# BV100011_ControlAO.net
KiCad netlist of a schematic drawn in Altium Designer
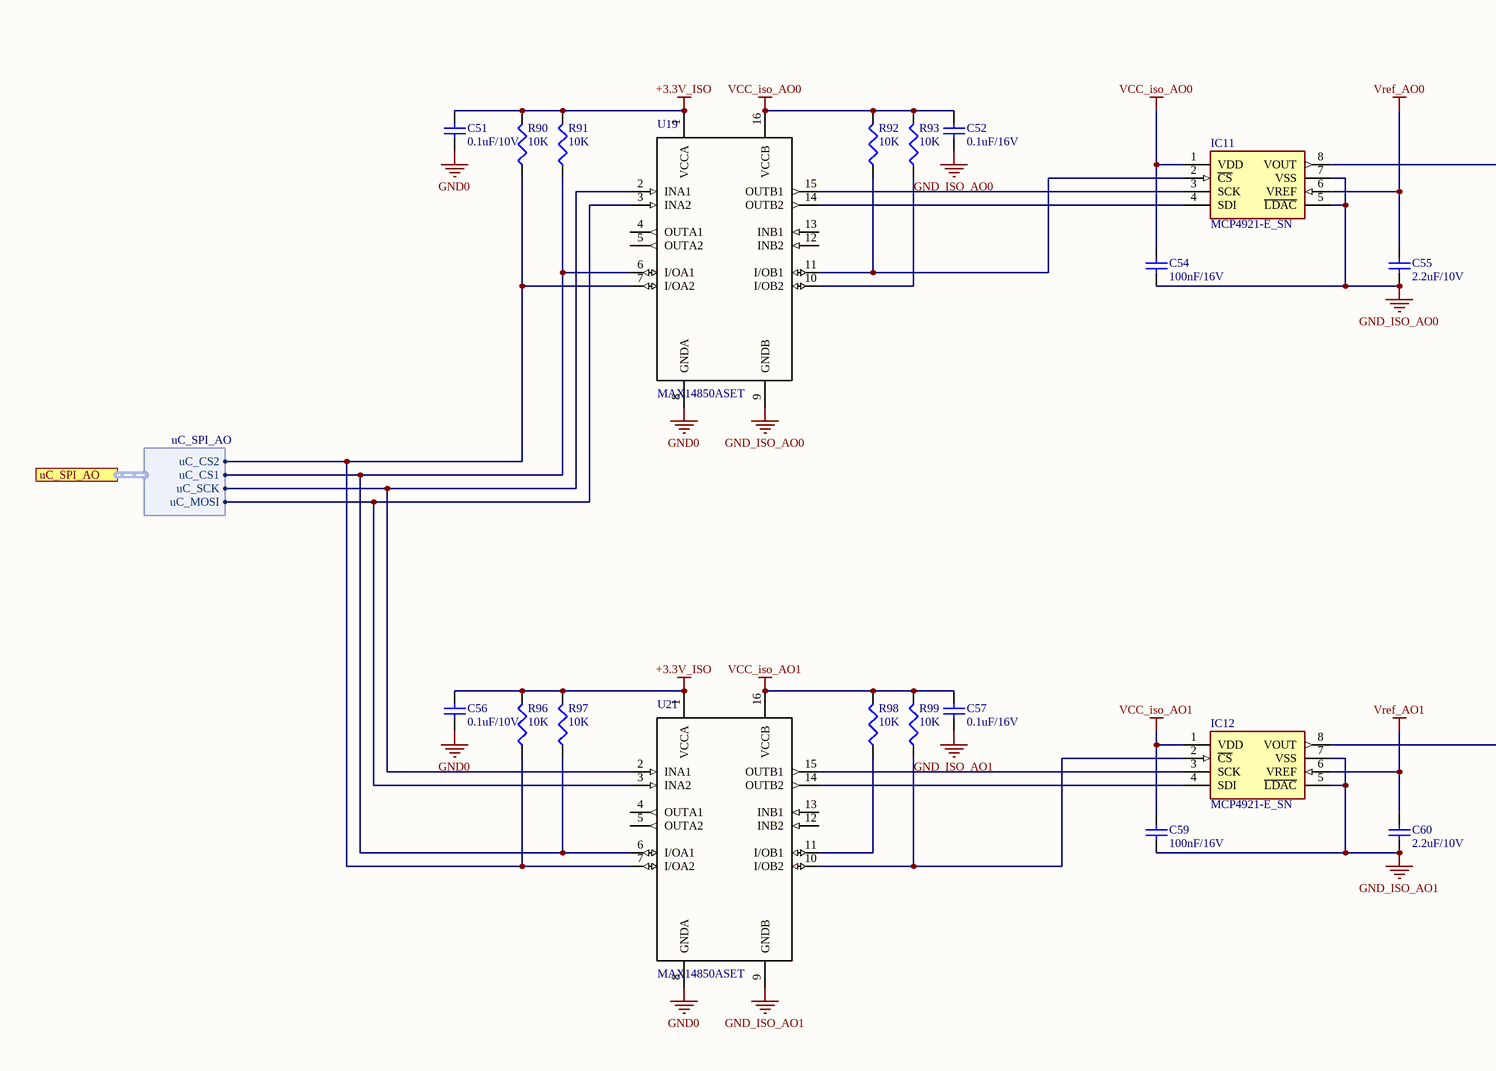
[diagram p0: BV100011_ControlAO.SchDoc, left]
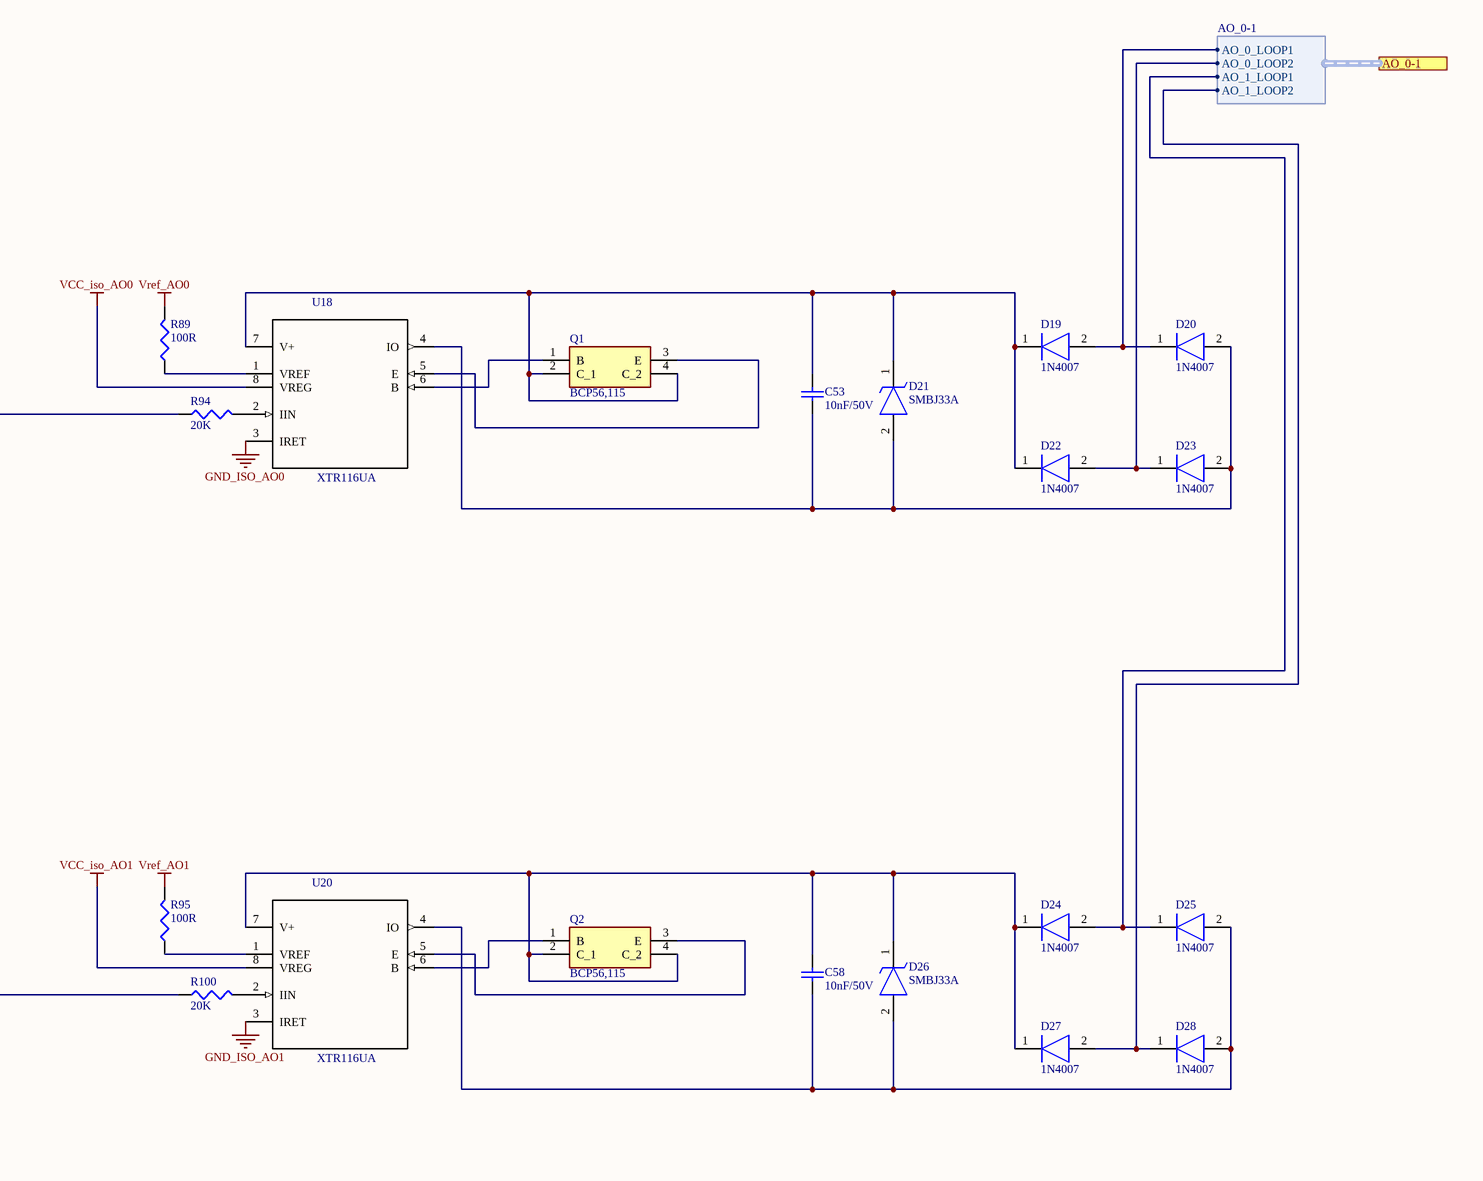
[diagram p1: BV100011_ControlAO.SchDoc, right]

(export (version "E")
  (design (tool "Eeschema 10.0.6"))
  (components
    (comp (ref "C51")
      (value "0.1uF/10V")
      (footprint "C1206")
      (description "Capacitor (Semiconductor SIM Model)")
      (fields (field (name "PUBLISHER") "Altium Limited"))
      (libsource (lib "Miscellaneous Devices") (part "Cap Semi"))
    )
    (comp (ref "C52")
      (value "0.1uF/16V")
      (footprint "C1206")
      (description "Capacitor (Semiconductor SIM Model)")
      (fields (field (name "PUBLISHER") "Altium Limited"))
      (libsource (lib "Miscellaneous Devices") (part "Cap Semi"))
    )
    (comp (ref "C53")
      (value "10nF/50V")
      (footprint "C1210")
      (description "Capacitor (Semiconductor SIM Model)")
      (fields (field (name "PUBLISHER") "Altium Limited"))
      (libsource (lib "Miscellaneous Devices") (part "Cap Semi"))
    )
    (comp (ref "C54")
      (value "100nF/16V")
      (footprint "C1206")
      (description "Capacitor (Semiconductor SIM Model)")
      (fields (field (name "PUBLISHER") "Altium Limited"))
      (libsource (lib "Miscellaneous Devices") (part "Cap Semi"))
    )
    (comp (ref "C55")
      (value "2.2uF/10V")
      (footprint "C1206")
      (description "Capacitor (Semiconductor SIM Model)")
      (fields (field (name "PUBLISHER") "Altium Limited"))
      (libsource (lib "Miscellaneous Devices") (part "Cap Semi"))
    )
    (comp (ref "C56")
      (value "0.1uF/10V")
      (footprint "C1206")
      (description "Capacitor (Semiconductor SIM Model)")
      (fields (field (name "PUBLISHER") "Altium Limited"))
      (libsource (lib "Miscellaneous Devices") (part "Cap Semi"))
    )
    (comp (ref "C57")
      (value "0.1uF/16V")
      (footprint "C1206")
      (description "Capacitor (Semiconductor SIM Model)")
      (fields (field (name "PUBLISHER") "Altium Limited"))
      (libsource (lib "Miscellaneous Devices") (part "Cap Semi"))
    )
    (comp (ref "C58")
      (value "10nF/50V")
      (footprint "C1210")
      (description "Capacitor (Semiconductor SIM Model)")
      (fields (field (name "PUBLISHER") "Altium Limited"))
      (libsource (lib "Miscellaneous Devices") (part "Cap Semi"))
    )
    (comp (ref "C59")
      (value "100nF/16V")
      (footprint "C1206")
      (description "Capacitor (Semiconductor SIM Model)")
      (fields (field (name "PUBLISHER") "Altium Limited"))
      (libsource (lib "Miscellaneous Devices") (part "Cap Semi"))
    )
    (comp (ref "C60")
      (value "2.2uF/10V")
      (footprint "C1206")
      (description "Capacitor (Semiconductor SIM Model)")
      (fields (field (name "PUBLISHER") "Altium Limited"))
      (libsource (lib "Miscellaneous Devices") (part "Cap Semi"))
    )
    (comp (ref "D19")
      (value "1N4007")
      (footprint "DIOM5327X242N")
      (description "Diode")
      (libsource (lib "1N4007") (part "1N4007"))
    )
    (comp (ref "D20")
      (value "1N4007")
      (footprint "DIOM5327X242N")
      (description "Diode")
      (libsource (lib "1N4007") (part "1N4007"))
    )
    (comp (ref "D21")
      (value "SMBJ33A")
      (footprint "DIOM5336X265N")
      (description "TVS Diode (Uni-directional)")
      (fields (field (name "MOUSER PART NUMBER") "512-SMBJ33A") (field (name "RS PART NUMBER") "8022320P"))
      (libsource (lib "SMBJ33A") (part "SMBJ33A"))
    )
    (comp (ref "D22")
      (value "1N4007")
      (footprint "DIOM5327X242N")
      (description "Diode")
      (libsource (lib "1N4007") (part "1N4007"))
    )
    (comp (ref "D23")
      (value "1N4007")
      (footprint "DIOM5327X242N")
      (description "Diode")
      (libsource (lib "1N4007") (part "1N4007"))
    )
    (comp (ref "D24")
      (value "1N4007")
      (footprint "DIOM5327X242N")
      (description "Diode")
      (libsource (lib "1N4007") (part "1N4007"))
    )
    (comp (ref "D25")
      (value "1N4007")
      (footprint "DIOM5327X242N")
      (description "Diode")
      (libsource (lib "1N4007") (part "1N4007"))
    )
    (comp (ref "D26")
      (value "SMBJ33A")
      (footprint "DIOM5336X265N")
      (description "TVS Diode (Uni-directional)")
      (fields (field (name "MOUSER PART NUMBER") "512-SMBJ33A") (field (name "RS PART NUMBER") "8022320P"))
      (libsource (lib "SMBJ33A") (part "SMBJ33A"))
    )
    (comp (ref "D27")
      (value "1N4007")
      (footprint "DIOM5327X242N")
      (description "Diode")
      (libsource (lib "1N4007") (part "1N4007"))
    )
    (comp (ref "D28")
      (value "1N4007")
      (footprint "DIOM5327X242N")
      (description "Diode")
      (libsource (lib "1N4007") (part "1N4007"))
    )
    (comp (ref "IC11")
      (value "MCP4921-E_SN")
      (footprint "SOIC127P600X175-8N")
      (description "Integrated Circuit")
      (fields
        (field (name "MANUFACTURER_PART_NUMBER") "MCP4921-E/SN")
        (field (name "MOUSER PART NUMBER") "579-MCP4921-E/SN")
      )
      (libsource (lib "MCP4921") (part "MCP4921-E_SN"))
    )
    (comp (ref "IC12")
      (value "MCP4921-E_SN")
      (footprint "SOIC127P600X175-8N")
      (description "Integrated Circuit")
      (fields
        (field (name "MANUFACTURER_PART_NUMBER") "MCP4921-E/SN")
        (field (name "MOUSER PART NUMBER") "579-MCP4921-E/SN")
      )
      (libsource (lib "MCP4921") (part "MCP4921-E_SN"))
    )
    (comp (ref "Q1")
      (value "BCP56,115")
      (footprint "SOT230P700X180-4N")
      (description "Transistor BJT NPN")
      (fields (field (name "MOUSER PART NUMBER") "771-BCP56-T/R") (field (name "RS PART NUMBER") "1125453P"))
      (libsource (lib "BCP56") (part "BCP56,115"))
    )
    (comp (ref "Q2")
      (value "BCP56,115")
      (footprint "SOT230P700X180-4N")
      (description "Transistor BJT NPN")
      (fields (field (name "MOUSER PART NUMBER") "771-BCP56-T/R") (field (name "RS PART NUMBER") "1125453P"))
      (libsource (lib "BCP56") (part "BCP56,115"))
    )
    (comp (ref "R89")
      (value "100R")
      (footprint "J1-0603")
      (description "Resistor")
      (fields (field (name "PUBLISHER") "Altium Limited"))
      (libsource (lib "Miscellaneous Devices") (part "Res3"))
    )
    (comp (ref "R90")
      (value "10K")
      (footprint "J1-0603")
      (description "Resistor")
      (fields (field (name "PUBLISHER") "Altium Limited"))
      (libsource (lib "Miscellaneous Devices") (part "Res3"))
    )
    (comp (ref "R91")
      (value "10K")
      (footprint "J1-0603")
      (description "Resistor")
      (fields (field (name "PUBLISHER") "Altium Limited"))
      (libsource (lib "Miscellaneous Devices") (part "Res3"))
    )
    (comp (ref "R92")
      (value "10K")
      (footprint "J1-0603")
      (description "Resistor")
      (fields (field (name "PUBLISHER") "Altium Limited"))
      (libsource (lib "Miscellaneous Devices") (part "Res3"))
    )
    (comp (ref "R93")
      (value "10K")
      (footprint "J1-0603")
      (description "Resistor")
      (fields (field (name "PUBLISHER") "Altium Limited"))
      (libsource (lib "Miscellaneous Devices") (part "Res3"))
    )
    (comp (ref "R94")
      (value "20K")
      (footprint "J1-0603")
      (description "Resistor")
      (fields (field (name "PUBLISHER") "Altium Limited"))
      (libsource (lib "Miscellaneous Devices") (part "Res3"))
    )
    (comp (ref "R95")
      (value "100R")
      (footprint "J1-0603")
      (description "Resistor")
      (fields (field (name "PUBLISHER") "Altium Limited"))
      (libsource (lib "Miscellaneous Devices") (part "Res3"))
    )
    (comp (ref "R96")
      (value "10K")
      (footprint "J1-0603")
      (description "Resistor")
      (fields (field (name "PUBLISHER") "Altium Limited"))
      (libsource (lib "Miscellaneous Devices") (part "Res3"))
    )
    (comp (ref "R97")
      (value "10K")
      (footprint "J1-0603")
      (description "Resistor")
      (fields (field (name "PUBLISHER") "Altium Limited"))
      (libsource (lib "Miscellaneous Devices") (part "Res3"))
    )
    (comp (ref "R98")
      (value "10K")
      (footprint "J1-0603")
      (description "Resistor")
      (fields (field (name "PUBLISHER") "Altium Limited"))
      (libsource (lib "Miscellaneous Devices") (part "Res3"))
    )
    (comp (ref "R99")
      (value "10K")
      (footprint "J1-0603")
      (description "Resistor")
      (fields (field (name "PUBLISHER") "Altium Limited"))
      (libsource (lib "Miscellaneous Devices") (part "Res3"))
    )
    (comp (ref "R100")
      (value "20K")
      (footprint "J1-0603")
      (description "Resistor")
      (fields (field (name "PUBLISHER") "Altium Limited"))
      (libsource (lib "Miscellaneous Devices") (part "Res3"))
    )
    (comp (ref "U18")
      (value "XTR116UA")
      (footprint "*SOIC127P600X175-8N")
      (description "Sensors, Sensor Conditioning, 4-20mA Transmitters 4-20mA Current Loop Transmitters")
      (fields (field (name "MF") "Texas Instruments"))
      (libsource (lib "XTR116UA") (part "XTR116UA"))
    )
    (comp (ref "U19")
      (value "MAX14850ASET")
      (footprint "*SOIC127P600X175-16N")
      (description "Digital Isolator, 6-Ch, 30ns, Nsoic-16")
      (fields (field (name "MF") "Maxim Integrated") (field (name "MP") "MAX14850ASE+"))
      (libsource (lib "MAX14850ASET") (part "MAX14850ASET"))
    )
    (comp (ref "U20")
      (value "XTR116UA")
      (footprint "*SOIC127P600X175-8N")
      (description "Sensors, Sensor Conditioning, 4-20mA Transmitters 4-20mA Current Loop Transmitters")
      (fields (field (name "MF") "Texas Instruments"))
      (libsource (lib "XTR116UA") (part "XTR116UA"))
    )
    (comp (ref "U21")
      (value "MAX14850ASET")
      (footprint "*SOIC127P600X175-16N")
      (description "Digital Isolator, 6-Ch, 30ns, Nsoic-16")
      (fields (field (name "MF") "Maxim Integrated") (field (name "MP") "MAX14850ASE+"))
      (libsource (lib "MAX14850ASET") (part "MAX14850ASET"))
    )
  )
  (nets
    (net (code "3") (name "+3.3V_ISO") (class "Default")
      (node (ref "C51") (pin "1") (pinfunction "1_1") (pintype "passive"))
      (node (ref "C56") (pin "1") (pinfunction "1_1") (pintype "passive"))
      (node (ref "R90") (pin "2") (pinfunction "2_2") (pintype "passive"))
      (node (ref "R91") (pin "2") (pinfunction "2_2") (pintype "passive"))
      (node (ref "R96") (pin "2") (pinfunction "2_2") (pintype "passive"))
      (node (ref "R97") (pin "2") (pinfunction "2_2") (pintype "passive"))
      (node (ref "U19") (pin "1") (pinfunction "VCCA_1") (pintype "power_in"))
      (node (ref "U21") (pin "1") (pinfunction "VCCA_1") (pintype "power_in"))
    )
    (net (code "6") (name "GND0") (class "Default")
      (node (ref "C51") (pin "2") (pinfunction "2_2") (pintype "passive"))
      (node (ref "C56") (pin "2") (pinfunction "2_2") (pintype "passive"))
      (node (ref "U19") (pin "8") (pinfunction "GNDA_8") (pintype "power_in"))
      (node (ref "U21") (pin "8") (pinfunction "GNDA_8") (pintype "power_in"))
    )
    (net (code "7") (name "GND_ISO_AO0") (class "Default")
      (node (ref "C52") (pin "2") (pinfunction "2_2") (pintype "passive"))
      (node (ref "C54") (pin "1") (pinfunction "1_1") (pintype "passive"))
      (node (ref "C55") (pin "1") (pinfunction "1_1") (pintype "passive"))
      (node (ref "IC11") (pin "5") (pinfunction "~{LDAC}_5") (pintype "passive"))
      (node (ref "IC11") (pin "7") (pinfunction "VSS_7") (pintype "power_in"))
      (node (ref "U18") (pin "3") (pinfunction "IRET_3") (pintype "passive"))
      (node (ref "U19") (pin "9") (pinfunction "GNDB_9") (pintype "power_in"))
    )
    (net (code "8") (name "GND_ISO_AO1") (class "Default")
      (node (ref "C57") (pin "2") (pinfunction "2_2") (pintype "passive"))
      (node (ref "C59") (pin "1") (pinfunction "1_1") (pintype "passive"))
      (node (ref "C60") (pin "1") (pinfunction "1_1") (pintype "passive"))
      (node (ref "IC12") (pin "5") (pinfunction "~{LDAC}_5") (pintype "passive"))
      (node (ref "IC12") (pin "7") (pinfunction "VSS_7") (pintype "power_in"))
      (node (ref "U20") (pin "3") (pinfunction "IRET_3") (pintype "passive"))
      (node (ref "U21") (pin "9") (pinfunction "GNDB_9") (pintype "power_in"))
    )
    (net (code "9") (name "Net-(D19-A)") (class "Default")
      (node (ref "D19") (pin "2") (pinfunction "A_2") (pintype "passive"))
      (node (ref "D20") (pin "1") (pinfunction "K_1") (pintype "passive"))
    )
    (net (code "10") (name "Net-(D19-K)") (class "Default")
      (node (ref "C53") (pin "2") (pinfunction "2_2") (pintype "passive"))
      (node (ref "D19") (pin "1") (pinfunction "K_1") (pintype "passive"))
      (node (ref "D21") (pin "1") (pinfunction "K_1") (pintype "passive"))
      (node (ref "D22") (pin "1") (pinfunction "K_1") (pintype "passive"))
      (node (ref "Q1") (pin "2") (pinfunction "C_1_2") (pintype "passive"))
      (node (ref "Q1") (pin "4") (pinfunction "C_2_4") (pintype "passive"))
      (node (ref "U18") (pin "7") (pinfunction "V+_7") (pintype "power_in"))
    )
    (net (code "11") (name "Net-(D20-A)") (class "Default")
      (node (ref "C53") (pin "1") (pinfunction "1_1") (pintype "passive"))
      (node (ref "D20") (pin "2") (pinfunction "A_2") (pintype "passive"))
      (node (ref "D21") (pin "2") (pinfunction "A_2") (pintype "passive"))
      (node (ref "D23") (pin "2") (pinfunction "A_2") (pintype "passive"))
      (node (ref "U18") (pin "4") (pinfunction "IO_4") (pintype "output"))
    )
    (net (code "12") (name "Net-(D22-A)") (class "Default")
      (node (ref "D22") (pin "2") (pinfunction "A_2") (pintype "passive"))
      (node (ref "D23") (pin "1") (pinfunction "K_1") (pintype "passive"))
    )
    (net (code "13") (name "Net-(D24-A)") (class "Default")
      (node (ref "D24") (pin "2") (pinfunction "A_2") (pintype "passive"))
      (node (ref "D25") (pin "1") (pinfunction "K_1") (pintype "passive"))
    )
    (net (code "14") (name "Net-(D24-K)") (class "Default")
      (node (ref "C58") (pin "2") (pinfunction "2_2") (pintype "passive"))
      (node (ref "D24") (pin "1") (pinfunction "K_1") (pintype "passive"))
      (node (ref "D26") (pin "1") (pinfunction "K_1") (pintype "passive"))
      (node (ref "D27") (pin "1") (pinfunction "K_1") (pintype "passive"))
      (node (ref "Q2") (pin "2") (pinfunction "C_1_2") (pintype "passive"))
      (node (ref "Q2") (pin "4") (pinfunction "C_2_4") (pintype "passive"))
      (node (ref "U20") (pin "7") (pinfunction "V+_7") (pintype "power_in"))
    )
    (net (code "15") (name "Net-(D25-A)") (class "Default")
      (node (ref "C58") (pin "1") (pinfunction "1_1") (pintype "passive"))
      (node (ref "D25") (pin "2") (pinfunction "A_2") (pintype "passive"))
      (node (ref "D26") (pin "2") (pinfunction "A_2") (pintype "passive"))
      (node (ref "D28") (pin "2") (pinfunction "A_2") (pintype "passive"))
      (node (ref "U20") (pin "4") (pinfunction "IO_4") (pintype "output"))
    )
    (net (code "16") (name "Net-(D27-A)") (class "Default")
      (node (ref "D27") (pin "2") (pinfunction "A_2") (pintype "passive"))
      (node (ref "D28") (pin "1") (pinfunction "K_1") (pintype "passive"))
    )
    (net (code "17") (name "Net-(IC11-SCK)") (class "Default")
      (node (ref "IC11") (pin "3") (pinfunction "SCK_3") (pintype "passive"))
      (node (ref "U19") (pin "15") (pinfunction "OUTB1_15") (pintype "output"))
    )
    (net (code "18") (name "Net-(IC11-SDI)") (class "Default")
      (node (ref "IC11") (pin "4") (pinfunction "SDI_4") (pintype "passive"))
      (node (ref "U19") (pin "14") (pinfunction "OUTB2_14") (pintype "output"))
    )
    (net (code "19") (name "Net-(IC11-VOUT)") (class "Default")
      (node (ref "IC11") (pin "8") (pinfunction "VOUT_8") (pintype "output"))
      (node (ref "R94") (pin "1") (pinfunction "1_1") (pintype "passive"))
    )
    (net (code "20") (name "Net-(IC11-~{CS})") (class "Default")
      (node (ref "IC11") (pin "2") (pinfunction "~{CS}_2") (pintype "input"))
      (node (ref "R92") (pin "1") (pinfunction "1_1") (pintype "passive"))
      (node (ref "U19") (pin "11") (pinfunction "I/OB1_11") (pintype "bidirectional"))
    )
    (net (code "21") (name "Net-(IC12-SCK)") (class "Default")
      (node (ref "IC12") (pin "3") (pinfunction "SCK_3") (pintype "passive"))
      (node (ref "U21") (pin "15") (pinfunction "OUTB1_15") (pintype "output"))
    )
    (net (code "22") (name "Net-(IC12-SDI)") (class "Default")
      (node (ref "IC12") (pin "4") (pinfunction "SDI_4") (pintype "passive"))
      (node (ref "U21") (pin "14") (pinfunction "OUTB2_14") (pintype "output"))
    )
    (net (code "23") (name "Net-(IC12-VOUT)") (class "Default")
      (node (ref "IC12") (pin "8") (pinfunction "VOUT_8") (pintype "output"))
      (node (ref "R100") (pin "1") (pinfunction "1_1") (pintype "passive"))
    )
    (net (code "24") (name "Net-(IC12-~{CS})") (class "Default")
      (node (ref "IC12") (pin "2") (pinfunction "~{CS}_2") (pintype "input"))
      (node (ref "R99") (pin "1") (pinfunction "1_1") (pintype "passive"))
      (node (ref "U21") (pin "10") (pinfunction "I/OB2_10") (pintype "bidirectional"))
    )
    (net (code "25") (name "Net-(Q1-B)") (class "Default")
      (node (ref "Q1") (pin "1") (pinfunction "B_1") (pintype "passive"))
      (node (ref "U18") (pin "6") (pinfunction "B_6") (pintype "input"))
    )
    (net (code "26") (name "Net-(Q1-E)") (class "Default")
      (node (ref "Q1") (pin "3") (pinfunction "E_3") (pintype "passive"))
      (node (ref "U18") (pin "5") (pinfunction "E_5") (pintype "input"))
    )
    (net (code "27") (name "Net-(Q2-B)") (class "Default")
      (node (ref "Q2") (pin "1") (pinfunction "B_1") (pintype "passive"))
      (node (ref "U20") (pin "6") (pinfunction "B_6") (pintype "input"))
    )
    (net (code "28") (name "Net-(Q2-E)") (class "Default")
      (node (ref "Q2") (pin "3") (pinfunction "E_3") (pintype "passive"))
      (node (ref "U20") (pin "5") (pinfunction "E_5") (pintype "input"))
    )
    (net (code "29") (name "Net-(U18-IIN)") (class "Default")
      (node (ref "R94") (pin "2") (pinfunction "2_2") (pintype "passive"))
      (node (ref "U18") (pin "2") (pinfunction "IIN_2") (pintype "input"))
    )
    (net (code "30") (name "Net-(U18-VREF)") (class "Default")
      (node (ref "R89") (pin "1") (pinfunction "1_1") (pintype "passive"))
      (node (ref "U18") (pin "1") (pinfunction "VREF_1") (pintype "passive"))
    )
    (net (code "31") (name "Net-(U19-INA1)") (class "Default")
      (node (ref "U19") (pin "2") (pinfunction "INA1_2") (pintype "input"))
      (node (ref "U21") (pin "2") (pinfunction "INA1_2") (pintype "input"))
    )
    (net (code "32") (name "Net-(U19-INA2)") (class "Default")
      (node (ref "U19") (pin "3") (pinfunction "INA2_3") (pintype "input"))
      (node (ref "U21") (pin "3") (pinfunction "INA2_3") (pintype "input"))
    )
    (net (code "33") (name "Net-(U19-I{slash}OA1)") (class "Default")
      (node (ref "R91") (pin "1") (pinfunction "1_1") (pintype "passive"))
      (node (ref "R97") (pin "1") (pinfunction "1_1") (pintype "passive"))
      (node (ref "U19") (pin "6") (pinfunction "I/OA1_6") (pintype "bidirectional"))
      (node (ref "U21") (pin "6") (pinfunction "I/OA1_6") (pintype "bidirectional"))
    )
    (net (code "34") (name "Net-(U19-I{slash}OA2)") (class "Default")
      (node (ref "R90") (pin "1") (pinfunction "1_1") (pintype "passive"))
      (node (ref "R96") (pin "1") (pinfunction "1_1") (pintype "passive"))
      (node (ref "U19") (pin "7") (pinfunction "I/OA2_7") (pintype "bidirectional"))
      (node (ref "U21") (pin "7") (pinfunction "I/OA2_7") (pintype "bidirectional"))
    )
    (net (code "35") (name "Net-(U19-I{slash}OB2)") (class "Default")
      (node (ref "R93") (pin "1") (pinfunction "1_1") (pintype "passive"))
      (node (ref "U19") (pin "10") (pinfunction "I/OB2_10") (pintype "bidirectional"))
    )
    (net (code "36") (name "Net-(U20-IIN)") (class "Default")
      (node (ref "R100") (pin "2") (pinfunction "2_2") (pintype "passive"))
      (node (ref "U20") (pin "2") (pinfunction "IIN_2") (pintype "input"))
    )
    (net (code "37") (name "Net-(U20-VREF)") (class "Default")
      (node (ref "R95") (pin "1") (pinfunction "1_1") (pintype "passive"))
      (node (ref "U20") (pin "1") (pinfunction "VREF_1") (pintype "passive"))
    )
    (net (code "38") (name "Net-(U21-I{slash}OB1)") (class "Default")
      (node (ref "R98") (pin "1") (pinfunction "1_1") (pintype "passive"))
      (node (ref "U21") (pin "11") (pinfunction "I/OB1_11") (pintype "bidirectional"))
    )
    (net (code "39") (name "VCC_iso_AO0") (class "Default")
      (node (ref "C52") (pin "1") (pinfunction "1_1") (pintype "passive"))
      (node (ref "C54") (pin "2") (pinfunction "2_2") (pintype "passive"))
      (node (ref "IC11") (pin "1") (pinfunction "VDD_1") (pintype "power_in"))
      (node (ref "R92") (pin "2") (pinfunction "2_2") (pintype "passive"))
      (node (ref "R93") (pin "2") (pinfunction "2_2") (pintype "passive"))
      (node (ref "U18") (pin "8") (pinfunction "VREG_8") (pintype "passive"))
      (node (ref "U19") (pin "16") (pinfunction "VCCB_16") (pintype "power_in"))
    )
    (net (code "40") (name "VCC_iso_AO1") (class "Default")
      (node (ref "C57") (pin "1") (pinfunction "1_1") (pintype "passive"))
      (node (ref "C59") (pin "2") (pinfunction "2_2") (pintype "passive"))
      (node (ref "IC12") (pin "1") (pinfunction "VDD_1") (pintype "power_in"))
      (node (ref "R98") (pin "2") (pinfunction "2_2") (pintype "passive"))
      (node (ref "R99") (pin "2") (pinfunction "2_2") (pintype "passive"))
      (node (ref "U20") (pin "8") (pinfunction "VREG_8") (pintype "passive"))
      (node (ref "U21") (pin "16") (pinfunction "VCCB_16") (pintype "power_in"))
    )
    (net (code "41") (name "Vref_AO0") (class "Default")
      (node (ref "C55") (pin "2") (pinfunction "2_2") (pintype "passive"))
      (node (ref "IC11") (pin "6") (pinfunction "VREF_6") (pintype "input"))
      (node (ref "R89") (pin "2") (pinfunction "2_2") (pintype "passive"))
    )
    (net (code "42") (name "Vref_AO1") (class "Default")
      (node (ref "C60") (pin "2") (pinfunction "2_2") (pintype "passive"))
      (node (ref "IC12") (pin "6") (pinfunction "VREF_6") (pintype "input"))
      (node (ref "R95") (pin "2") (pinfunction "2_2") (pintype "passive"))
    )
    (net (code "43") (name "unconnected-(U19-INB1-Pad13)") (class "Default")
      (node (ref "U19") (pin "13") (pinfunction "INB1_13") (pintype "input"))
    )
    (net (code "44") (name "unconnected-(U19-INB2-Pad12)") (class "Default")
      (node (ref "U19") (pin "12") (pinfunction "INB2_12") (pintype "input"))
    )
    (net (code "45") (name "unconnected-(U19-OUTA1-Pad4)") (class "Default")
      (node (ref "U19") (pin "4") (pinfunction "OUTA1_4") (pintype "output"))
    )
    (net (code "46") (name "unconnected-(U19-OUTA2-Pad5)") (class "Default")
      (node (ref "U19") (pin "5") (pinfunction "OUTA2_5") (pintype "output"))
    )
    (net (code "47") (name "unconnected-(U21-INB1-Pad13)") (class "Default")
      (node (ref "U21") (pin "13") (pinfunction "INB1_13") (pintype "input"))
    )
    (net (code "48") (name "unconnected-(U21-INB2-Pad12)") (class "Default")
      (node (ref "U21") (pin "12") (pinfunction "INB2_12") (pintype "input"))
    )
    (net (code "49") (name "unconnected-(U21-OUTA1-Pad4)") (class "Default")
      (node (ref "U21") (pin "4") (pinfunction "OUTA1_4") (pintype "output"))
    )
    (net (code "50") (name "unconnected-(U21-OUTA2-Pad5)") (class "Default")
      (node (ref "U21") (pin "5") (pinfunction "OUTA2_5") (pintype "output"))
    )
  )
)
